# psu.net
KiCad netlist of a schematic drawn in EAGLE
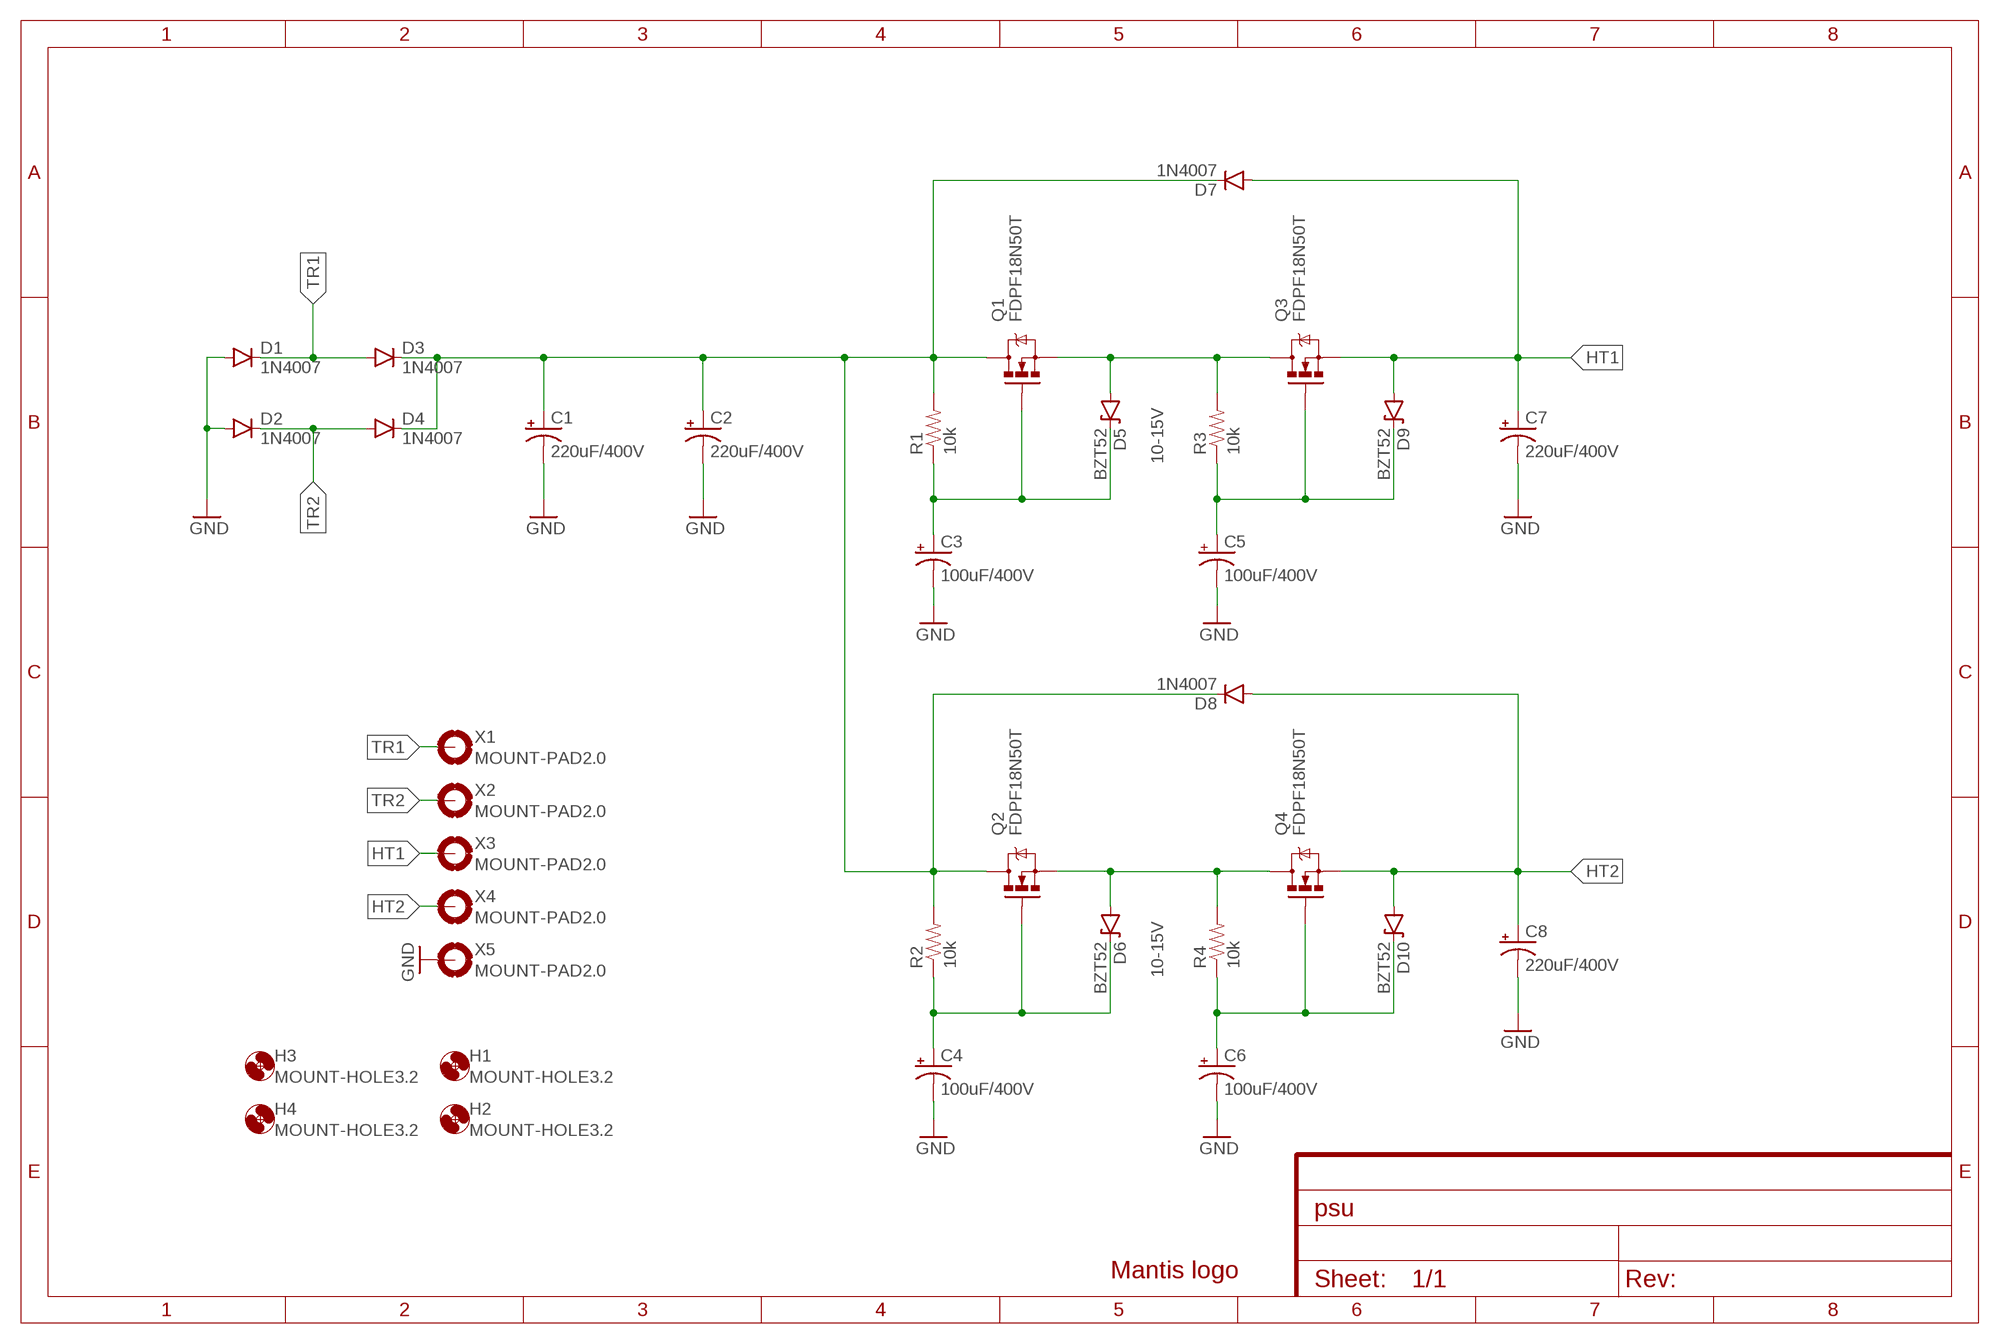
[diagram p0: schematic, sheet 1]

(export (version "E")
  (design (tool "Eeschema 10.0.6"))
  (components
    (comp (ref "C1")
      (value "220uF/400V")
      (footprint "eagle-import:CPOL-RADIAL-25_12.5")
      (libsource (lib "eagle-import") (part "CAP_POLPTH-25/12.5"))
    )
    (comp (ref "C2")
      (value "220uF/400V")
      (footprint "eagle-import:CPOL-RADIAL-25_12.5")
      (libsource (lib "eagle-import") (part "CAP_POLPTH-25/12.5"))
    )
    (comp (ref "C3")
      (value "100uF/400V")
      (footprint "eagle-import:CPOL-RADIAL-16_7.5")
      (libsource (lib "eagle-import") (part "CAP_POLPTH-16/7.5"))
    )
    (comp (ref "C4")
      (value "100uF/400V")
      (footprint "eagle-import:CPOL-RADIAL-16_7.5")
      (libsource (lib "eagle-import") (part "CAP_POLPTH-16/7.5"))
    )
    (comp (ref "C5")
      (value "100uF/400V")
      (footprint "eagle-import:CPOL-RADIAL-16_7.5")
      (libsource (lib "eagle-import") (part "CAP_POLPTH-16/7.5"))
    )
    (comp (ref "C6")
      (value "100uF/400V")
      (footprint "eagle-import:CPOL-RADIAL-16_7.5")
      (libsource (lib "eagle-import") (part "CAP_POLPTH-16/7.5"))
    )
    (comp (ref "C7")
      (value "220uF/400V")
      (footprint "eagle-import:CPOL-RADIAL-25_12.5")
      (libsource (lib "eagle-import") (part "CAP_POLPTH-25/12.5"))
    )
    (comp (ref "C8")
      (value "220uF/400V")
      (footprint "eagle-import:CPOL-RADIAL-25_12.5")
      (libsource (lib "eagle-import") (part "CAP_POLPTH-25/12.5"))
    )
    (comp (ref "D1")
      (value "1N4007")
      (footprint "eagle-import:DIODE-1N4001")
      (libsource (lib "eagle-import") (part "DIODEPTH"))
    )
    (comp (ref "D2")
      (value "1N4007")
      (footprint "eagle-import:DIODE-1N4001")
      (libsource (lib "eagle-import") (part "DIODEPTH"))
    )
    (comp (ref "D3")
      (value "1N4007")
      (footprint "eagle-import:DIODE-1N4001")
      (libsource (lib "eagle-import") (part "DIODEPTH"))
    )
    (comp (ref "D4")
      (value "1N4007")
      (footprint "eagle-import:DIODE-1N4001")
      (libsource (lib "eagle-import") (part "DIODEPTH"))
    )
    (comp (ref "D5")
      (value "BZT52")
      (footprint "eagle-import:DIODE-BZT52")
      (libsource (lib "eagle-import") (part "DIODE-ZENER"))
    )
    (comp (ref "D6")
      (value "BZT52")
      (footprint "eagle-import:DIODE-BZT52")
      (libsource (lib "eagle-import") (part "DIODE-ZENER"))
    )
    (comp (ref "D7")
      (value "1N4007")
      (footprint "eagle-import:DIODE-1N4001")
      (libsource (lib "eagle-import") (part "DIODEPTH"))
    )
    (comp (ref "D8")
      (value "1N4007")
      (footprint "eagle-import:DIODE-1N4001")
      (libsource (lib "eagle-import") (part "DIODEPTH"))
    )
    (comp (ref "D9")
      (value "BZT52")
      (footprint "eagle-import:DIODE-BZT52")
      (libsource (lib "eagle-import") (part "DIODE-ZENER"))
    )
    (comp (ref "D10")
      (value "BZT52")
      (footprint "eagle-import:DIODE-BZT52")
      (libsource (lib "eagle-import") (part "DIODE-ZENER"))
    )
    (comp (ref "H1")
      (value "MOUNT-HOLE3.2")
      (footprint "eagle-import:3,2")
      (libsource (lib "eagle-import") (part "MOUNT-HOLE3.2"))
    )
    (comp (ref "H2")
      (value "MOUNT-HOLE3.2")
      (footprint "eagle-import:3,2")
      (libsource (lib "eagle-import") (part "MOUNT-HOLE3.2"))
    )
    (comp (ref "H3")
      (value "MOUNT-HOLE3.2")
      (footprint "eagle-import:3,2")
      (libsource (lib "eagle-import") (part "MOUNT-HOLE3.2"))
    )
    (comp (ref "H4")
      (value "MOUNT-HOLE3.2")
      (footprint "eagle-import:3,2")
      (libsource (lib "eagle-import") (part "MOUNT-HOLE3.2"))
    )
    (comp (ref "LOGO1")
      (value "LOGO-MANTIS")
      (footprint "eagle-import:LOGO-MANTIS")
      (libsource (lib "eagle-import") (part "LOGO-MANTIS"))
    )
    (comp (ref "Q1")
      (value "FDPF18N50T")
      (footprint "eagle-import:TO220V")
      (libsource (lib "eagle-import") (part "FDPF18N50T"))
    )
    (comp (ref "Q2")
      (value "FDPF18N50T")
      (footprint "eagle-import:TO220V")
      (libsource (lib "eagle-import") (part "FDPF18N50T"))
    )
    (comp (ref "Q3")
      (value "FDPF18N50T")
      (footprint "eagle-import:TO220V")
      (libsource (lib "eagle-import") (part "FDPF18N50T"))
    )
    (comp (ref "Q4")
      (value "FDPF18N50T")
      (footprint "eagle-import:TO220V")
      (libsource (lib "eagle-import") (part "FDPF18N50T"))
    )
    (comp (ref "R1")
      (value "10k")
      (footprint "eagle-import:AXIAL-0.4")
      (libsource (lib "eagle-import") (part "RESISTORPTH-1/4W"))
    )
    (comp (ref "R2")
      (value "10k")
      (footprint "eagle-import:AXIAL-0.4")
      (libsource (lib "eagle-import") (part "RESISTORPTH-1/4W"))
    )
    (comp (ref "R3")
      (value "10k")
      (footprint "eagle-import:AXIAL-0.4")
      (libsource (lib "eagle-import") (part "RESISTORPTH-1/4W"))
    )
    (comp (ref "R4")
      (value "10k")
      (footprint "eagle-import:AXIAL-0.4")
      (libsource (lib "eagle-import") (part "RESISTORPTH-1/4W"))
    )
    (comp (ref "X1")
      (value "MOUNT-PAD2.0")
      (footprint "eagle-import:2.0-PAD")
      (libsource (lib "eagle-import") (part "MOUNT-PAD2.0"))
    )
    (comp (ref "X2")
      (value "MOUNT-PAD2.0")
      (footprint "eagle-import:2.0-PAD")
      (libsource (lib "eagle-import") (part "MOUNT-PAD2.0"))
    )
    (comp (ref "X3")
      (value "MOUNT-PAD2.0")
      (footprint "eagle-import:2.0-PAD")
      (libsource (lib "eagle-import") (part "MOUNT-PAD2.0"))
    )
    (comp (ref "X4")
      (value "MOUNT-PAD2.0")
      (footprint "eagle-import:2.0-PAD")
      (libsource (lib "eagle-import") (part "MOUNT-PAD2.0"))
    )
    (comp (ref "X5")
      (value "MOUNT-PAD2.0")
      (footprint "eagle-import:2.0-PAD")
      (libsource (lib "eagle-import") (part "MOUNT-PAD2.0"))
    )
  )
  (nets
    (net (code "1") (name "GND") (class "Default")
      (node (ref "C1") (pin "2") (pinfunction "-_2") (pintype "passive"))
      (node (ref "C2") (pin "2") (pinfunction "-_2") (pintype "passive"))
      (node (ref "C3") (pin "2") (pinfunction "-_2") (pintype "passive"))
      (node (ref "C4") (pin "2") (pinfunction "-_2") (pintype "passive"))
      (node (ref "C5") (pin "2") (pinfunction "-_2") (pintype "passive"))
      (node (ref "C6") (pin "2") (pinfunction "-_2") (pintype "passive"))
      (node (ref "C7") (pin "2") (pinfunction "-_2") (pintype "passive"))
      (node (ref "C8") (pin "2") (pinfunction "-_2") (pintype "passive"))
      (node (ref "D1") (pin "A") (pinfunction "A_A") (pintype "passive"))
      (node (ref "D2") (pin "A") (pinfunction "A_A") (pintype "passive"))
      (node (ref "X5") (pin "P$1") (pinfunction "MOUNT_P$1") (pintype "passive"))
    )
    (net (code "2") (name "HT1") (class "Default")
      (node (ref "C7") (pin "1") (pinfunction "+_1") (pintype "passive"))
      (node (ref "D7") (pin "A") (pinfunction "A_A") (pintype "passive"))
      (node (ref "D9") (pin "A") (pinfunction "A_A") (pintype "passive"))
      (node (ref "Q3") (pin "3") (pinfunction "S_3") (pintype "passive"))
      (node (ref "X3") (pin "P$1") (pinfunction "MOUNT_P$1") (pintype "passive"))
    )
    (net (code "3") (name "HT2") (class "Default")
      (node (ref "C8") (pin "1") (pinfunction "+_1") (pintype "passive"))
      (node (ref "D10") (pin "A") (pinfunction "A_A") (pintype "passive"))
      (node (ref "D8") (pin "A") (pinfunction "A_A") (pintype "passive"))
      (node (ref "Q4") (pin "3") (pinfunction "S_3") (pintype "passive"))
      (node (ref "X4") (pin "P$1") (pinfunction "MOUNT_P$1") (pintype "passive"))
    )
    (net (code "4") (name "Net-(C1-+)") (class "Default")
      (node (ref "C1") (pin "1") (pinfunction "+_1") (pintype "passive"))
      (node (ref "C2") (pin "1") (pinfunction "+_1") (pintype "passive"))
      (node (ref "D3") (pin "C") (pinfunction "C_C") (pintype "passive"))
      (node (ref "D4") (pin "C") (pinfunction "C_C") (pintype "passive"))
      (node (ref "D7") (pin "C") (pinfunction "C_C") (pintype "passive"))
      (node (ref "D8") (pin "C") (pinfunction "C_C") (pintype "passive"))
      (node (ref "Q1") (pin "2") (pinfunction "D_2") (pintype "passive"))
      (node (ref "Q2") (pin "2") (pinfunction "D_2") (pintype "passive"))
      (node (ref "R1") (pin "P$2") (pinfunction "2_P$2") (pintype "passive"))
      (node (ref "R2") (pin "P$2") (pinfunction "2_P$2") (pintype "passive"))
    )
    (net (code "5") (name "Net-(C3-+)") (class "Default")
      (node (ref "C3") (pin "1") (pinfunction "+_1") (pintype "passive"))
      (node (ref "D5") (pin "C") (pinfunction "C_C") (pintype "passive"))
      (node (ref "Q1") (pin "1") (pinfunction "G_1") (pintype "passive"))
      (node (ref "R1") (pin "P$1") (pinfunction "1_P$1") (pintype "passive"))
    )
    (net (code "6") (name "Net-(C4-+)") (class "Default")
      (node (ref "C4") (pin "1") (pinfunction "+_1") (pintype "passive"))
      (node (ref "D6") (pin "C") (pinfunction "C_C") (pintype "passive"))
      (node (ref "Q2") (pin "1") (pinfunction "G_1") (pintype "passive"))
      (node (ref "R2") (pin "P$1") (pinfunction "1_P$1") (pintype "passive"))
    )
    (net (code "7") (name "Net-(C5-+)") (class "Default")
      (node (ref "C5") (pin "1") (pinfunction "+_1") (pintype "passive"))
      (node (ref "D9") (pin "C") (pinfunction "C_C") (pintype "passive"))
      (node (ref "Q3") (pin "1") (pinfunction "G_1") (pintype "passive"))
      (node (ref "R3") (pin "P$1") (pinfunction "1_P$1") (pintype "passive"))
    )
    (net (code "8") (name "Net-(C6-+)") (class "Default")
      (node (ref "C6") (pin "1") (pinfunction "+_1") (pintype "passive"))
      (node (ref "D10") (pin "C") (pinfunction "C_C") (pintype "passive"))
      (node (ref "Q4") (pin "1") (pinfunction "G_1") (pintype "passive"))
      (node (ref "R4") (pin "P$1") (pinfunction "1_P$1") (pintype "passive"))
    )
    (net (code "9") (name "Net-(Q1-S)") (class "Default")
      (node (ref "D5") (pin "A") (pinfunction "A_A") (pintype "passive"))
      (node (ref "Q1") (pin "3") (pinfunction "S_3") (pintype "passive"))
      (node (ref "Q3") (pin "2") (pinfunction "D_2") (pintype "passive"))
      (node (ref "R3") (pin "P$2") (pinfunction "2_P$2") (pintype "passive"))
    )
    (net (code "10") (name "Net-(Q2-S)") (class "Default")
      (node (ref "D6") (pin "A") (pinfunction "A_A") (pintype "passive"))
      (node (ref "Q2") (pin "3") (pinfunction "S_3") (pintype "passive"))
      (node (ref "Q4") (pin "2") (pinfunction "D_2") (pintype "passive"))
      (node (ref "R4") (pin "P$2") (pinfunction "2_P$2") (pintype "passive"))
    )
    (net (code "11") (name "TR1") (class "Default")
      (node (ref "D1") (pin "C") (pinfunction "C_C") (pintype "passive"))
      (node (ref "D3") (pin "A") (pinfunction "A_A") (pintype "passive"))
      (node (ref "X1") (pin "P$1") (pinfunction "MOUNT_P$1") (pintype "passive"))
    )
    (net (code "12") (name "TR2") (class "Default")
      (node (ref "D2") (pin "C") (pinfunction "C_C") (pintype "passive"))
      (node (ref "D4") (pin "A") (pinfunction "A_A") (pintype "passive"))
      (node (ref "X2") (pin "P$1") (pinfunction "MOUNT_P$1") (pintype "passive"))
    )
  )
)
